# HV_PSU.net
KiCad netlist of a schematic drawn in Altium Designer
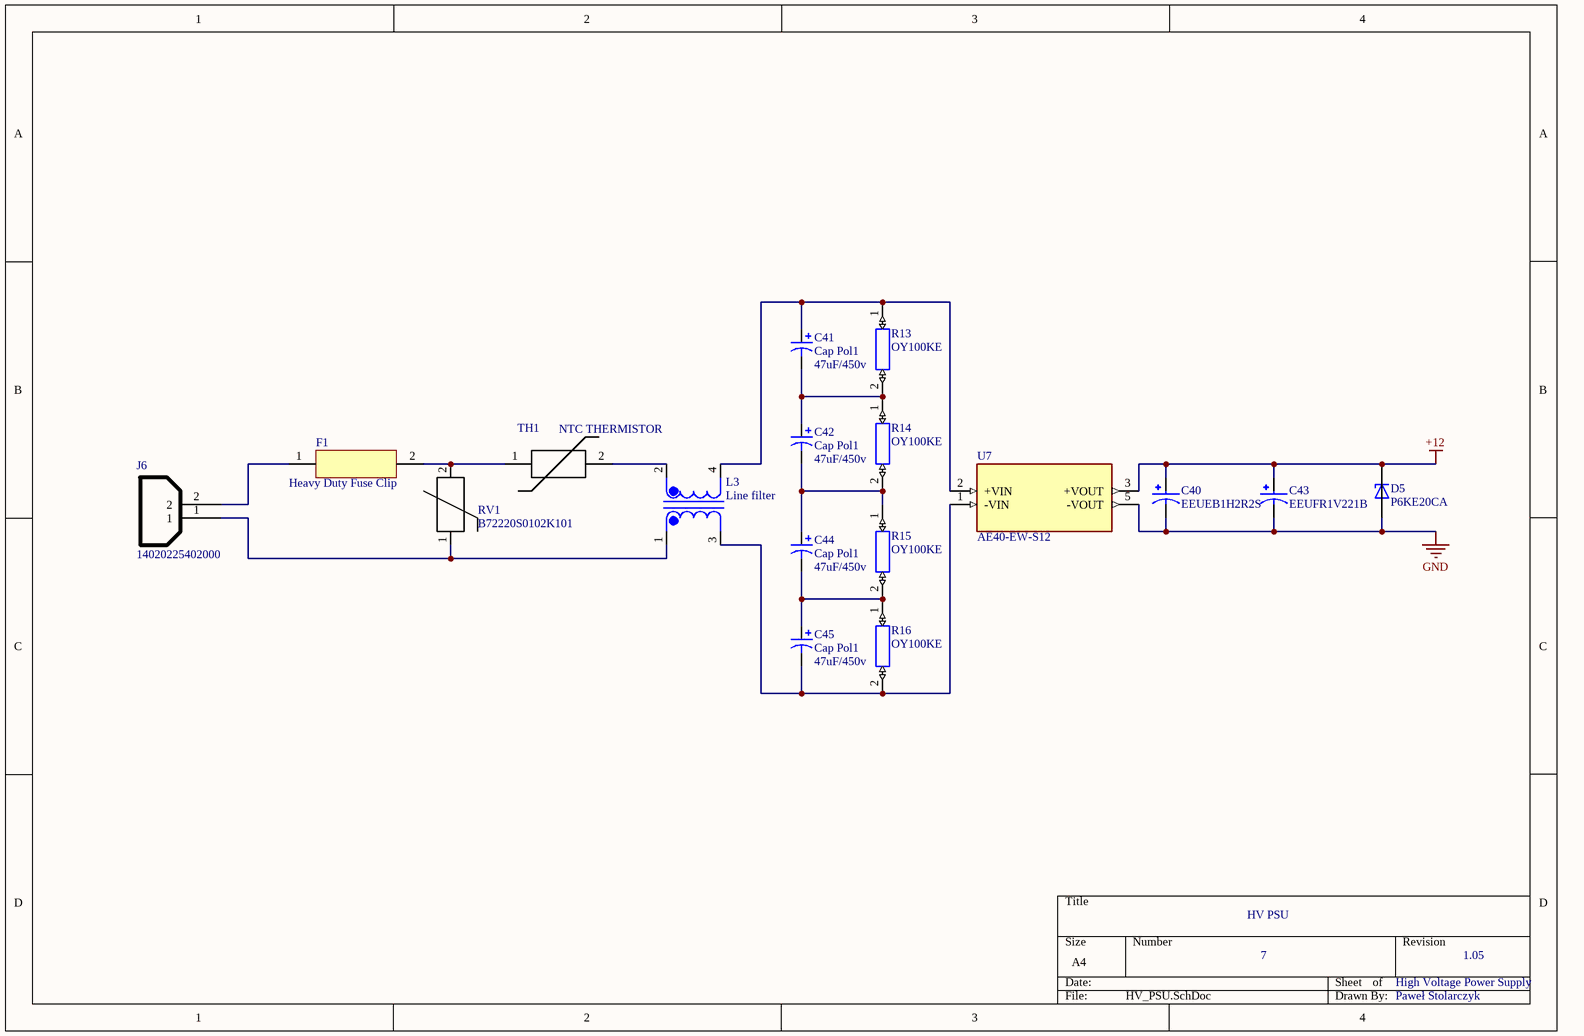
[diagram p0: HV_PSU.SchDoc]

(export (version "E")
  (design (tool "Eeschema 10.0.6"))
  (components
    (comp (ref "C40")
      (value "EEUEB1H2R2S")
      (footprint "CAPPRD200W50D500H1100")
      (fields (field (name "MF") "Panasonic"))
      (libsource (lib "EEUEB1H2R2S") (part "EEUEB1H2R2S"))
    )
    (comp (ref "C41")
      (value "Cap Pol1")
      (footprint "RB7.6-15")
      (description "Polarized Capacitor (Radial)")
      (fields (field (name "ALTIUM_VALUE") "47uF/450v") (field (name "PUBLISHER") "Altium Limited"))
      (libsource (lib "Miscellaneous Devices") (part "Cap Pol1"))
    )
    (comp (ref "C42")
      (value "Cap Pol1")
      (footprint "RB7.6-15")
      (description "Polarized Capacitor (Radial)")
      (fields (field (name "ALTIUM_VALUE") "47uF/450v") (field (name "PUBLISHER") "Altium Limited"))
      (libsource (lib "Miscellaneous Devices") (part "Cap Pol1"))
    )
    (comp (ref "C43")
      (value "EEUFR1V221B")
      (footprint "CAPPRD500W60D800H1150")
      (description "Aluminum Electrolytic Capacitors - Radial Leaded 35VDC 220uF 20% L/S=5mm")
      (fields (field (name "MF") "Panasonic") (field (name "MP") "EEU-FR1V221B"))
      (libsource (lib "EEUFR1V221B") (part "EEUFR1V221B"))
    )
    (comp (ref "C44")
      (value "Cap Pol1")
      (footprint "RB7.6-15")
      (description "Polarized Capacitor (Radial)")
      (fields (field (name "ALTIUM_VALUE") "47uF/450v") (field (name "PUBLISHER") "Altium Limited"))
      (libsource (lib "Miscellaneous Devices") (part "Cap Pol1"))
    )
    (comp (ref "C45")
      (value "Cap Pol1")
      (footprint "RB7.6-15")
      (description "Polarized Capacitor (Radial)")
      (fields (field (name "ALTIUM_VALUE") "47uF/450v") (field (name "PUBLISHER") "Altium Limited"))
      (libsource (lib "Miscellaneous Devices") (part "Cap Pol1"))
    )
    (comp (ref "D5")
      (value "P6KE20CA")
      (footprint "DIOAD1300W80L670D310")
      (description "600W, 20V, 5%, Bidirectional, TVS")
      (fields (field (name "MF") "Taiwan Semiconductor"))
      (libsource (lib "P6KE20CA") (part "P6KE20CA"))
    )
    (comp (ref "F1")
      (value "Heavy Duty Fuse Clip")
      (footprint "8040.2012.01")
      (description "THT; 10x38mm; 15A")
      (libsource (lib "8040.2012.01") (part "8040.2012.01"))
    )
    (comp (ref "J6")
      (value "14020225402000")
      (footprint "14020225402000")
      (libsource (lib "14020225402000") (part "14020225402000"))
    )
    (comp (ref "L3")
      (value "Line filter")
      (footprint "SCF29XV-070-1R2A030JV")
      (description "THT; 9,9mH; 19,2mΩ; -40÷150°C; SCF")
      (fields (field (name "MF") "KEMET") (field (name "MP") "SCF-02-1300"))
      (libsource (lib "SCF-02-1300") (part "SCF29XV-070-1R2A030JV"))
    )
    (comp (ref "R13")
      (value "OY100KE")
      (footprint "RESAD4700W80L1900D700")
      (description "10 Ohms Â±10% 2W Through Hole Resistor Axial Moisture Resistant, Pulse Withstanding Ceramic")
      (fields (field (name "MF") "Ohmite"))
      (libsource (lib "OY100KE") (part "OY100KE"))
    )
    (comp (ref "R14")
      (value "OY100KE")
      (footprint "RESAD4700W80L1900D700")
      (description "10 Ohms Â±10% 2W Through Hole Resistor Axial Moisture Resistant, Pulse Withstanding Ceramic")
      (fields (field (name "MF") "Ohmite"))
      (libsource (lib "OY100KE") (part "OY100KE"))
    )
    (comp (ref "R15")
      (value "OY100KE")
      (footprint "RESAD4700W80L1900D700")
      (description "10 Ohms Â±10% 2W Through Hole Resistor Axial Moisture Resistant, Pulse Withstanding Ceramic")
      (fields (field (name "MF") "Ohmite"))
      (libsource (lib "OY100KE") (part "OY100KE"))
    )
    (comp (ref "R16")
      (value "OY100KE")
      (footprint "RESAD4700W80L1900D700")
      (description "10 Ohms Â±10% 2W Through Hole Resistor Axial Moisture Resistant, Pulse Withstanding Ceramic")
      (fields (field (name "MF") "Ohmite"))
      (libsource (lib "OY100KE") (part "OY100KE"))
    )
    (comp (ref "RV1")
      (value "B72220S0102K101")
      (footprint "VAR_B72220S0102K101")
      (description "Var MOV 1100VAC/1465VDC 6500A 1800V Thru-Hole Radial Automotive Bulk")
      (fields (field (name "MF") "TDK ELECTRONICS"))
      (libsource (lib "B72220S0102K101") (part "B72220S0102K101"))
    )
    (comp (ref "TH1")
      (value "NTC THERMISTOR")
      (footprint "MF72-10D20M")
      (description "10Ω; 23mm; ±20%; THT; 2700K")
      (libsource (lib "MF72-10D20M") (part "MF72-10D20M"))
    )
    (comp (ref "U7")
      (value "AE40-EW-S12")
      (footprint "CONV_AE40-EW-S12")
      (description "40 W, 6:1 Input Range, Single Regulated Output,  7 Pin DIP, 4000 Vdc Isolation, Dc-Dc Converter")
      (fields (field (name "MF") "CUI Inc."))
      (libsource (lib "AE40-EW-S12") (part "AE40-EW-S12"))
    )
  )
  (nets
    (net (code "1") (name "+12") (class "Default")
      (node (ref "C40") (pin "P") (pinfunction "P_P") (pintype "passive"))
      (node (ref "C43") (pin "P") (pinfunction "P_P") (pintype "passive"))
      (node (ref "D5") (pin "C") (pinfunction "C_C") (pintype "passive"))
      (node (ref "U7") (pin "3") (pinfunction "+VOUT_3") (pintype "output"))
    )
    (net (code "2") (name "GND") (class "Default")
      (node (ref "C40") (pin "N") (pinfunction "N_N") (pintype "passive"))
      (node (ref "C43") (pin "N") (pinfunction "N_N") (pintype "passive"))
      (node (ref "D5") (pin "A") (pinfunction "A_A") (pintype "passive"))
      (node (ref "U7") (pin "5") (pinfunction "-VOUT_5") (pintype "output"))
    )
    (net (code "3") (name "Net-(C41-Pad2)") (class "Default")
      (node (ref "C41") (pin "2") (pinfunction "2_2") (pintype "passive"))
      (node (ref "C42") (pin "1") (pinfunction "1_1") (pintype "passive"))
      (node (ref "R13") (pin "2") (pinfunction "2_2") (pintype "bidirectional"))
      (node (ref "R14") (pin "1") (pinfunction "1_1") (pintype "bidirectional"))
    )
    (net (code "4") (name "Net-(C42-Pad2)") (class "Default")
      (node (ref "C42") (pin "2") (pinfunction "2_2") (pintype "passive"))
      (node (ref "C44") (pin "1") (pinfunction "1_1") (pintype "passive"))
      (node (ref "R14") (pin "2") (pinfunction "2_2") (pintype "bidirectional"))
      (node (ref "R15") (pin "1") (pinfunction "1_1") (pintype "bidirectional"))
    )
    (net (code "5") (name "Net-(C44-Pad2)") (class "Default")
      (node (ref "C44") (pin "2") (pinfunction "2_2") (pintype "passive"))
      (node (ref "C45") (pin "1") (pinfunction "1_1") (pintype "passive"))
      (node (ref "R15") (pin "2") (pinfunction "2_2") (pintype "bidirectional"))
      (node (ref "R16") (pin "1") (pinfunction "1_1") (pintype "bidirectional"))
    )
    (net (code "6") (name "Net-(F1-Pad1)") (class "Default")
      (node (ref "F1") (pin "1") (pinfunction "1_1") (pintype "passive"))
      (node (ref "J6") (pin "2") (pinfunction "2_2") (pintype "passive"))
    )
    (net (code "7") (name "Net-(F1-Pad2)") (class "Default")
      (node (ref "F1") (pin "2") (pinfunction "2_2") (pintype "passive"))
      (node (ref "RV1") (pin "2") (pinfunction "2_2") (pintype "passive"))
      (node (ref "TH1") (pin "1") (pinfunction "1_1") (pintype "passive"))
    )
    (net (code "8") (name "Net-(J6-Pad1)") (class "Default")
      (node (ref "J6") (pin "1") (pinfunction "1_1") (pintype "passive"))
      (node (ref "L3") (pin "1") (pinfunction "1_1") (pintype "passive"))
      (node (ref "RV1") (pin "1") (pinfunction "1_1") (pintype "passive"))
    )
    (net (code "9") (name "Net-(L3-Pad2)") (class "Default")
      (node (ref "L3") (pin "2") (pinfunction "2_2") (pintype "passive"))
      (node (ref "TH1") (pin "2") (pinfunction "2_2") (pintype "passive"))
    )
    (net (code "10") (name "Net-(U7-+VIN)") (class "Default")
      (node (ref "C41") (pin "1") (pinfunction "1_1") (pintype "passive"))
      (node (ref "L3") (pin "4") (pinfunction "4_4") (pintype "passive"))
      (node (ref "R13") (pin "1") (pinfunction "1_1") (pintype "bidirectional"))
      (node (ref "U7") (pin "2") (pinfunction "+VIN_2") (pintype "input"))
    )
    (net (code "11") (name "Net-(U7--VIN)") (class "Default")
      (node (ref "C45") (pin "2") (pinfunction "2_2") (pintype "passive"))
      (node (ref "L3") (pin "3") (pinfunction "3_3") (pintype "passive"))
      (node (ref "R16") (pin "2") (pinfunction "2_2") (pintype "bidirectional"))
      (node (ref "U7") (pin "1") (pinfunction "-VIN_1") (pintype "input"))
    )
  )
)
